# part2.net
KiCad netlist of a schematic drawn in Altium Designer
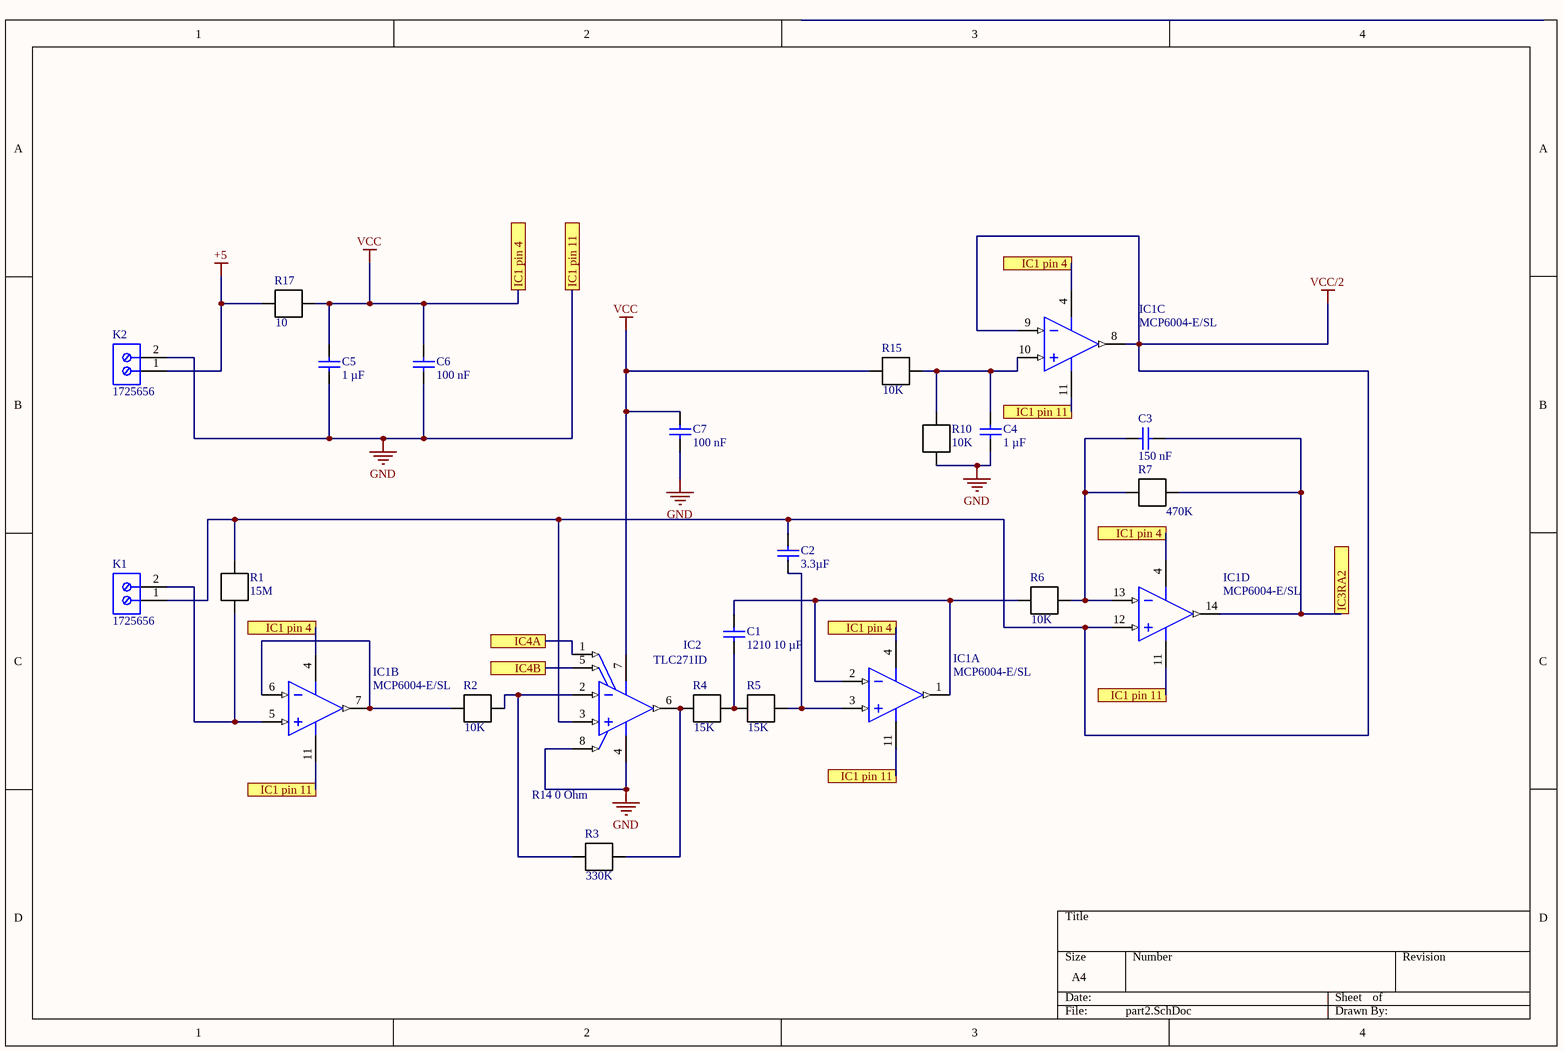
[diagram p0: part2.SchDoc]

(export (version "E")
  (design (tool "Eeschema 10.0.6"))
  (components
    (comp (ref "C1")
      (value "1210 10 µF")
      (footprint "CAPC3225X279X50LL20T25")
      (description "Chip Capacitor, 10 uF, +/- 10%, 25 V, -55 to 85 degC, 1210 (3225 Metric), RoHS, Tape and Reel")
      (fields (field (name "TOLERANCE") "±10%") (field (name "MANUFACTURER") "AVX"))
      (libsource (lib "Altium Content Vault") (part "CAP-NP-2"))
    )
    (comp (ref "C2")
      (value "3.3µF")
      (footprint "CAPC1210(3225)280_N")
      (description "CAP 2.2uF 100V ±10% 1210 (3225 Metric) Thickness 2.8mm SMD")
      (fields (field (name "TOLERANCE") "Â±10%"))
      (libsource (lib "Altium Content Vault") (part "CAP"))
    )
    (comp (ref "C3")
      (value "150 nF")
      (footprint "CAPC2013X70X45NL10T25")
      (fields (field (name "MANUFACTURER") "Murata") (field (name "PART NUMBER") "GRM2165C1H332JA01D"))
      (libsource (lib "Altium Content Vault") (part "CAP"))
    )
    (comp (ref "C4")
      (value "1 µF")
      (footprint "CAPC2013X70X45NL10T25")
      (fields (field (name "MANUFACTURER") "Murata") (field (name "PART NUMBER") "GRM2165C1H332JA01D"))
      (libsource (lib "Altium Content Vault") (part "CAP"))
    )
    (comp (ref "C5")
      (value "1 µF")
      (footprint "CAPC2013X70X45NL10T25")
      (fields (field (name "MANUFACTURER") "Murata") (field (name "PART NUMBER") "GRM2165C1H332JA01D"))
      (libsource (lib "Altium Content Vault") (part "CAP"))
    )
    (comp (ref "C6")
      (value "100 nF")
      (footprint "CAPC2013X70X45NL10T25")
      (fields (field (name "MANUFACTURER") "Murata") (field (name "PART NUMBER") "GRM2165C1H332JA01D"))
      (libsource (lib "Altium Content Vault") (part "CAP"))
    )
    (comp (ref "C7")
      (value "100 nF")
      (footprint "CAPC2013X70X45NL10T25")
      (fields (field (name "MANUFACTURER") "Murata") (field (name "PART NUMBER") "GRM2165C1H332JA01D"))
      (libsource (lib "Altium Content Vault") (part "CAP"))
    )
    (comp (ref "IC1")
      (value "MCP6004-E/SL")
      (footprint "SOIC-SL14_M")
      (description "1 MHz, Low-Power Operational Amplifier, 14-Pin SOIC, Extended Temperature")
      (libsource (lib "Altium Content Vault") (part "AMP-OPA-MCP6004-IL14"))
    )
    (comp (ref "IC2")
      (value "TLC271ID")
      (footprint "D0008A_L")
      (fields (field (name "MANUFACTURER") "Texas Instruments"))
      (libsource (lib "Altium Content Vault") (part "TI-TLC271X-X8"))
    )
    (comp (ref "K1")
      (value "1725656")
      (footprint "PHOE-1725656-2")
      (description "Male Header, Pitch 2.54 mm, 1 x 2 Position, Height 9 mm, Tail Length 3.5 mm")
      (fields (field (name "MANUFACTURER") "Phoenix Contact"))
      (libsource (lib "Altium Content Vault") (part "CN-1P-F-TB2"))
    )
    (comp (ref "K2")
      (value "1725656")
      (footprint "PHOE-1725656-2")
      (description "Male Header, Pitch 2.54 mm, 1 x 2 Position, Height 9 mm, Tail Length 3.5 mm")
      (fields (field (name "MANUFACTURER") "Phoenix Contact"))
      (libsource (lib "Altium Content Vault") (part "CN-1P-F-TB2"))
    )
    (comp (ref "R1")
      (value "15M")
      (footprint "6-0805_M")
      (description "Resistor")
      (fields (field (name "PUBLISHER") "Altium Limited"))
      (libsource (lib "bio_lamp") (part "Res1"))
    )
    (comp (ref "R2")
      (value "10K")
      (footprint "6-0805_M")
      (description "Resistor")
      (fields (field (name "PUBLISHER") "Altium Limited"))
      (libsource (lib "bio_lamp") (part "Res1"))
    )
    (comp (ref "R3")
      (value "330K")
      (footprint "C1206")
      (description "Resistor")
      (fields (field (name "PUBLISHER") "Altium Limited"))
      (libsource (lib "bio_lamp") (part "Res1"))
    )
    (comp (ref "R4")
      (value "15K")
      (footprint "C1206")
      (description "Resistor")
      (fields (field (name "PUBLISHER") "Altium Limited"))
      (libsource (lib "bio_lamp") (part "Res1"))
    )
    (comp (ref "R5")
      (value "15K")
      (footprint "C1206")
      (description "Resistor")
      (fields (field (name "PUBLISHER") "Altium Limited"))
      (libsource (lib "bio_lamp") (part "Res1"))
    )
    (comp (ref "R6")
      (value "10K")
      (footprint "6-0805_M")
      (description "Resistor")
      (fields (field (name "PUBLISHER") "Altium Limited"))
      (libsource (lib "bio_lamp") (part "Res1"))
    )
    (comp (ref "R7")
      (value "470K")
      (footprint "C1206")
      (description "Resistor")
      (fields (field (name "PUBLISHER") "Altium Limited"))
      (libsource (lib "bio_lamp") (part "Res1"))
    )
    (comp (ref "R10")
      (value "10K")
      (footprint "6-0805_M")
      (description "Resistor")
      (fields (field (name "PUBLISHER") "Altium Limited"))
      (libsource (lib "bio_lamp") (part "Res1"))
    )
    (comp (ref "R15")
      (value "10K")
      (footprint "6-0805_M")
      (description "Resistor")
      (fields (field (name "PUBLISHER") "Altium Limited"))
      (libsource (lib "bio_lamp") (part "Res1"))
    )
    (comp (ref "R17")
      (value "10")
      (footprint "6-0805_M")
      (description "Resistor")
      (fields (field (name "PUBLISHER") "Altium Limited"))
      (libsource (lib "bio_lamp") (part "Res1"))
    )
  )
  (nets
    (net (code "1") (name "+5") (class "Default")
      (node (ref "K2") (pin "1") (pinfunction "1_1") (pintype "passive"))
      (node (ref "R17") (pin "1") (pinfunction "1_1") (pintype "passive"))
    )
    (net (code "2") (name "/IC3RA2") (class "Default")
      (node (ref "C3") (pin "1") (pinfunction "1_1") (pintype "passive"))
      (node (ref "IC1") (pin "14") (pinfunction "VOUTD_14") (pintype "output"))
      (node (ref "R7") (pin "2") (pinfunction "2_2") (pintype "passive"))
    )
    (net (code "3") (name "/IC4A") (class "Default")
      (node (ref "IC2") (pin "1") (pinfunction "OFFSET_N1_1") (pintype "input"))
    )
    (net (code "4") (name "/IC4B") (class "Default")
      (node (ref "IC2") (pin "5") (pinfunction "OFFSET_N2_5") (pintype "input"))
    )
    (net (code "5") (name "GND") (class "Default")
      (node (ref "C4") (pin "1") (pinfunction "1_1") (pintype "passive"))
      (node (ref "C5") (pin "1") (pinfunction "1_1") (pintype "passive"))
      (node (ref "C6") (pin "1") (pinfunction "1_1") (pintype "passive"))
      (node (ref "C7") (pin "1") (pinfunction "1_1") (pintype "passive"))
      (node (ref "IC1") (pin "11") (pinfunction "VSS_11") (pintype "power_in"))
      (node (ref "IC2") (pin "4") (pinfunction "GND_4") (pintype "power_in"))
      (node (ref "IC2") (pin "8") (pinfunction "BIAS_SELECT_8") (pintype "input"))
      (node (ref "K2") (pin "2") (pinfunction "2_2") (pintype "passive"))
      (node (ref "R10") (pin "1") (pinfunction "1_1") (pintype "passive"))
    )
    (net (code "6") (name "Net-(C1-Pad1)") (class "Default")
      (node (ref "C1") (pin "1") (pinfunction "1_1") (pintype "passive"))
      (node (ref "R4") (pin "2") (pinfunction "2_2") (pintype "passive"))
      (node (ref "R5") (pin "1") (pinfunction "1_1") (pintype "passive"))
    )
    (net (code "7") (name "Net-(IC1A-VINA+)") (class "Default")
      (node (ref "C2") (pin "1") (pinfunction "1_1") (pintype "passive"))
      (node (ref "IC1") (pin "3") (pinfunction "VINA+_3") (pintype "input"))
      (node (ref "R5") (pin "2") (pinfunction "2_2") (pintype "passive"))
    )
    (net (code "8") (name "Net-(IC1A-VINA-)") (class "Default")
      (node (ref "C1") (pin "2") (pinfunction "2_2") (pintype "passive"))
      (node (ref "IC1") (pin "1") (pinfunction "VOUTA_1") (pintype "output"))
      (node (ref "IC1") (pin "2") (pinfunction "VINA-_2") (pintype "input"))
      (node (ref "R6") (pin "1") (pinfunction "1_1") (pintype "passive"))
    )
    (net (code "9") (name "Net-(IC1B-VINB+)") (class "Default")
      (node (ref "IC1") (pin "5") (pinfunction "VINB+_5") (pintype "input"))
      (node (ref "K1") (pin "2") (pinfunction "2_2") (pintype "passive"))
      (node (ref "R1") (pin "1") (pinfunction "1_1") (pintype "passive"))
    )
    (net (code "10") (name "Net-(IC1B-VINB-)") (class "Default")
      (node (ref "IC1") (pin "6") (pinfunction "VINB-_6") (pintype "input"))
      (node (ref "IC1") (pin "7") (pinfunction "VOUTB_7") (pintype "output"))
      (node (ref "R2") (pin "1") (pinfunction "1_1") (pintype "passive"))
    )
    (net (code "11") (name "Net-(IC1C-VINC+)") (class "Default")
      (node (ref "C4") (pin "2") (pinfunction "2_2") (pintype "passive"))
      (node (ref "IC1") (pin "10") (pinfunction "VINC+_10") (pintype "input"))
      (node (ref "R10") (pin "2") (pinfunction "2_2") (pintype "passive"))
      (node (ref "R15") (pin "2") (pinfunction "2_2") (pintype "passive"))
    )
    (net (code "12") (name "Net-(IC1D-VIND-)") (class "Default")
      (node (ref "C3") (pin "2") (pinfunction "2_2") (pintype "passive"))
      (node (ref "IC1") (pin "13") (pinfunction "VIND-_13") (pintype "input"))
      (node (ref "R6") (pin "2") (pinfunction "2_2") (pintype "passive"))
      (node (ref "R7") (pin "1") (pinfunction "1_1") (pintype "passive"))
    )
    (net (code "13") (name "Net-(IC2-IN-)") (class "Default")
      (node (ref "IC2") (pin "2") (pinfunction "IN-_2") (pintype "input"))
      (node (ref "R2") (pin "2") (pinfunction "2_2") (pintype "passive"))
      (node (ref "R3") (pin "1") (pinfunction "1_1") (pintype "passive"))
    )
    (net (code "14") (name "Net-(IC2-OUT)") (class "Default")
      (node (ref "IC2") (pin "6") (pinfunction "OUT_6") (pintype "output"))
      (node (ref "R3") (pin "2") (pinfunction "2_2") (pintype "passive"))
      (node (ref "R4") (pin "1") (pinfunction "1_1") (pintype "passive"))
    )
    (net (code "15") (name "VCC") (class "Default")
      (node (ref "C5") (pin "2") (pinfunction "2_2") (pintype "passive"))
      (node (ref "C6") (pin "2") (pinfunction "2_2") (pintype "passive"))
      (node (ref "C7") (pin "2") (pinfunction "2_2") (pintype "passive"))
      (node (ref "IC1") (pin "4") (pinfunction "VDD_4") (pintype "power_in"))
      (node (ref "IC2") (pin "7") (pinfunction "VDD_7") (pintype "power_in"))
      (node (ref "R15") (pin "1") (pinfunction "1_1") (pintype "passive"))
      (node (ref "R17") (pin "2") (pinfunction "2_2") (pintype "passive"))
    )
    (net (code "16") (name "VCC{slash}2") (class "Default")
      (node (ref "C2") (pin "2") (pinfunction "2_2") (pintype "passive"))
      (node (ref "IC1") (pin "12") (pinfunction "VIND+_12") (pintype "input"))
      (node (ref "IC1") (pin "8") (pinfunction "VOUTC_8") (pintype "output"))
      (node (ref "IC1") (pin "9") (pinfunction "VINC-_9") (pintype "input"))
      (node (ref "IC2") (pin "3") (pinfunction "IN+_3") (pintype "input"))
      (node (ref "K1") (pin "1") (pinfunction "1_1") (pintype "passive"))
      (node (ref "R1") (pin "2") (pinfunction "2_2") (pintype "passive"))
    )
  )
)
